# SpaceInvaders-v21-OtherMill-DoubleSided.net
KiCad netlist of a schematic drawn in EAGLE
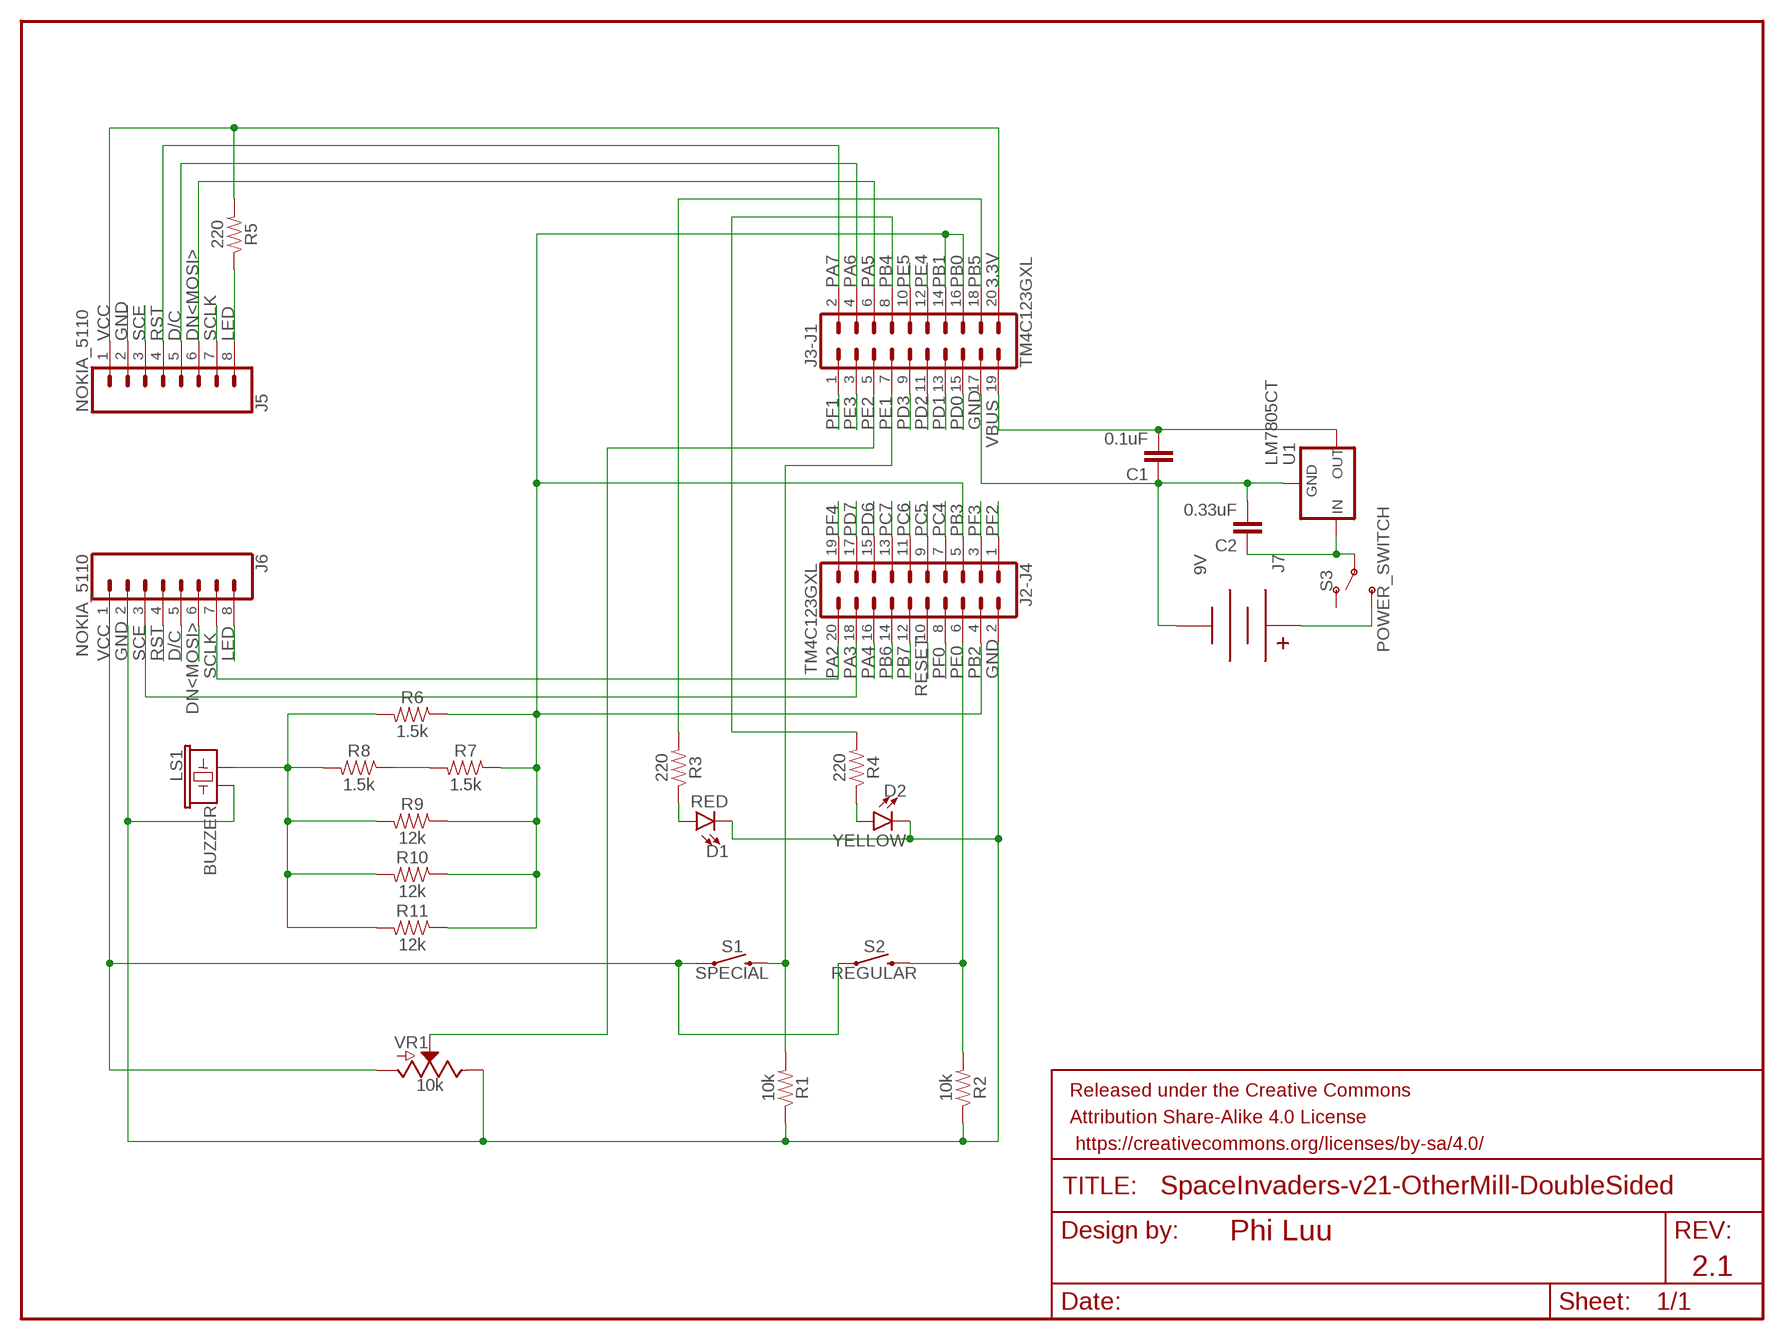
[diagram p0: schematic, sheet 1]

(export (version "E")
  (design (tool "Eeschema 10.0.6"))
  (components
    (comp (ref "C1")
      (value "0.1uF")
      (footprint "eagle-import:CAP-PTH-SMALL-KIT")
      (libsource (lib "eagle-import") (part "0.1UF-KIT-EZ-50V-20%"))
    )
    (comp (ref "C2")
      (value "0.33uF")
      (footprint "eagle-import:CAP-PTH-SMALL-KIT")
      (libsource (lib "eagle-import") (part "0.1UF-KIT-EZ-50V-20%"))
    )
    (comp (ref "D1")
      (value "RED")
      (footprint "eagle-import:LED_5MM")
      (libsource (lib "eagle-import") (part "LED5MM"))
    )
    (comp (ref "D2")
      (value "YELLOW")
      (footprint "eagle-import:LED_5MM")
      (libsource (lib "eagle-import") (part "LED5MM"))
    )
    (comp (ref "FRAME1")
      (value "FRAME-LETTER")
      (footprint "eagle-import:CREATIVE_COMMONS")
      (libsource (lib "eagle-import") (part "FRAME-LETTER"))
    )
    (comp (ref "J2-J4")
      (value "TM4C123GXL")
      (footprint "eagle-import:2X10")
      (libsource (lib "eagle-import") (part "CONN_10X2"))
    )
    (comp (ref "J3-J1")
      (value "TM4C123GXL")
      (footprint "eagle-import:2X10")
      (libsource (lib "eagle-import") (part "CONN_10X2"))
    )
    (comp (ref "J5")
      (value "NOKIA_5110")
      (footprint "eagle-import:1X08")
      (libsource (lib "eagle-import") (part "CONN_08{dblquote}"))
    )
    (comp (ref "J6")
      (value "NOKIA_5110")
      (footprint "eagle-import:1X08")
      (libsource (lib "eagle-import") (part "CONN_08{dblquote}"))
    )
    (comp (ref "J7")
      (value "9V")
      (footprint "eagle-import:BC9VPC")
      (libsource (lib "eagle-import") (part "BC9VPC"))
    )
    (comp (ref "LS1")
      (value "BUZZER")
      (footprint "eagle-import:BUZZER-12MM")
      (libsource (lib "eagle-import") (part "BUZZER-PTH"))
    )
    (comp (ref "R1")
      (value "10k")
      (footprint "eagle-import:AXIAL-0.3")
      (libsource (lib "eagle-import") (part "10KOHM-HORIZ-1/4W-5%"))
    )
    (comp (ref "R2")
      (value "10k")
      (footprint "eagle-import:AXIAL-0.3")
      (libsource (lib "eagle-import") (part "10KOHM-HORIZ-1/4W-5%"))
    )
    (comp (ref "R3")
      (value "220")
      (footprint "eagle-import:AXIAL-0.3")
      (libsource (lib "eagle-import") (part "1KOHM-HORIZ-1/4W-5%"))
    )
    (comp (ref "R4")
      (value "220")
      (footprint "eagle-import:AXIAL-0.3")
      (libsource (lib "eagle-import") (part "1KOHM-HORIZ-1/4W-5%"))
    )
    (comp (ref "R5")
      (value "220")
      (footprint "eagle-import:AXIAL-0.3")
      (libsource (lib "eagle-import") (part "1KOHM-HORIZ-1/4W-5%"))
    )
    (comp (ref "R6")
      (value "1.5k")
      (footprint "eagle-import:AXIAL-0.3")
      (libsource (lib "eagle-import") (part "1KOHM-HORIZ-1/4W-5%"))
    )
    (comp (ref "R7")
      (value "1.5k")
      (footprint "eagle-import:AXIAL-0.3")
      (libsource (lib "eagle-import") (part "1KOHM-HORIZ-1/4W-5%"))
    )
    (comp (ref "R8")
      (value "1.5k")
      (footprint "eagle-import:AXIAL-0.3")
      (libsource (lib "eagle-import") (part "1KOHM-HORIZ-1/4W-5%"))
    )
    (comp (ref "R9")
      (value "12k")
      (footprint "eagle-import:AXIAL-0.3")
      (libsource (lib "eagle-import") (part "1KOHM-HORIZ-1/4W-5%"))
    )
    (comp (ref "R10")
      (value "12k")
      (footprint "eagle-import:AXIAL-0.3")
      (libsource (lib "eagle-import") (part "1KOHM-HORIZ-1/4W-5%"))
    )
    (comp (ref "R11")
      (value "12k")
      (footprint "eagle-import:AXIAL-0.3")
      (libsource (lib "eagle-import") (part "1KOHM-HORIZ-1/4W-5%"))
    )
    (comp (ref "S1")
      (value "SPECIAL")
      (footprint "eagle-import:TACTILE_SWITCH_PTH_6.0MM")
      (libsource (lib "eagle-import") (part "MOMENTARY-SWITCH-SPST-PTH-6.0MM"))
    )
    (comp (ref "S2")
      (value "REGULAR")
      (footprint "eagle-import:TACTILE_SWITCH_PTH_6.0MM")
      (libsource (lib "eagle-import") (part "MOMENTARY-SWITCH-SPST-PTH-6.0MM"))
    )
    (comp (ref "S3")
      (value "POWER_SWITCH")
      (footprint "eagle-import:SWITCH_SPDT_PTH_11.6X4.0MM")
      (libsource (lib "eagle-import") (part "SWITCH-SPDT-PTH-11.6X4.0MM"))
    )
    (comp (ref "U1")
      (value "LM7805CT")
      (footprint "eagle-import:TO-220-ALT")
      (libsource (lib "eagle-import") (part "V_REG_78XX-TO-220"))
    )
    (comp (ref "VR1")
      (value "10k")
      (footprint "eagle-import:SLIDER-MEDIUM")
      (libsource (lib "eagle-import") (part "POTENTIOMETER_SLIDE-30MM-1/10W-20%"))
    )
  )
  (nets
    (net (code "1") (name "/3.3V") (class "Default")
      (node (ref "J3-J1") (pin "20") (pinfunction "20_20") (pintype "passive"))
      (node (ref "J5") (pin "1") (pinfunction "1_1") (pintype "passive"))
      (node (ref "J6") (pin "1") (pinfunction "1_1") (pintype "passive"))
      (node (ref "R5") (pin "P$2") (pinfunction "2_P$2") (pintype "passive"))
      (node (ref "S1") (pin "1") (pinfunction "1_1") (pintype "passive"))
      (node (ref "S2") (pin "1") (pinfunction "1_1") (pintype "passive"))
      (node (ref "VR1") (pin "BOTTOM") (pinfunction "A_BOTTOM") (pintype "passive"))
    )
    (net (code "2") (name "/GND") (class "Default")
      (node (ref "C1") (pin "1") (pinfunction "1_1") (pintype "passive"))
      (node (ref "C2") (pin "2") (pinfunction "2_2") (pintype "passive"))
      (node (ref "D1") (pin "K") (pinfunction "C_K") (pintype "passive"))
      (node (ref "D2") (pin "K") (pinfunction "C_K") (pintype "passive"))
      (node (ref "J2-J4") (pin "2") (pinfunction "2_2") (pintype "passive"))
      (node (ref "J3-J1") (pin "17") (pinfunction "17_17") (pintype "passive"))
      (node (ref "J5") (pin "2") (pinfunction "2_2") (pintype "passive"))
      (node (ref "J6") (pin "2") (pinfunction "2_2") (pintype "passive"))
      (node (ref "J7") (pin "V-") (pinfunction "V-_V-") (pintype "bidirectional"))
      (node (ref "LS1") (pin "-") (pinfunction "2_-") (pintype "passive"))
      (node (ref "R1") (pin "P$1") (pinfunction "1_P$1") (pintype "passive"))
      (node (ref "R2") (pin "P$1") (pinfunction "1_P$1") (pintype "passive"))
      (node (ref "U1") (pin "GND") (pinfunction "GND_GND") (pintype "input"))
      (node (ref "VR1") (pin "TOP") (pinfunction "E_TOP") (pintype "passive"))
    )
    (net (code "3") (name "/LED") (class "Default")
      (node (ref "J5") (pin "8") (pinfunction "8_8") (pintype "passive"))
      (node (ref "J6") (pin "8") (pinfunction "8_8") (pintype "passive"))
      (node (ref "R5") (pin "P$1") (pinfunction "1_P$1") (pintype "passive"))
    )
    (net (code "4") (name "/PA2") (class "Default")
      (node (ref "J2-J4") (pin "20") (pinfunction "20_20") (pintype "passive"))
      (node (ref "J5") (pin "7") (pinfunction "7_7") (pintype "passive"))
      (node (ref "J6") (pin "7") (pinfunction "7_7") (pintype "passive"))
    )
    (net (code "5") (name "/PA3") (class "Default")
      (node (ref "J2-J4") (pin "18") (pinfunction "18_18") (pintype "passive"))
      (node (ref "J5") (pin "3") (pinfunction "3_3") (pintype "passive"))
      (node (ref "J6") (pin "3") (pinfunction "3_3") (pintype "passive"))
    )
    (net (code "6") (name "/PA4") (class "Default")
      (node (ref "J2-J4") (pin "16") (pinfunction "16_16") (pintype "passive"))
    )
    (net (code "7") (name "/PA5") (class "Default")
      (node (ref "J3-J1") (pin "6") (pinfunction "6_6") (pintype "passive"))
      (node (ref "J5") (pin "6") (pinfunction "6_6") (pintype "passive"))
      (node (ref "J6") (pin "6") (pinfunction "6_6") (pintype "passive"))
    )
    (net (code "8") (name "/PA6") (class "Default")
      (node (ref "J3-J1") (pin "4") (pinfunction "4_4") (pintype "passive"))
      (node (ref "J5") (pin "5") (pinfunction "5_5") (pintype "passive"))
      (node (ref "J6") (pin "5") (pinfunction "5_5") (pintype "passive"))
    )
    (net (code "9") (name "/PA7") (class "Default")
      (node (ref "J3-J1") (pin "2") (pinfunction "2_2") (pintype "passive"))
      (node (ref "J5") (pin "4") (pinfunction "4_4") (pintype "passive"))
      (node (ref "J6") (pin "4") (pinfunction "4_4") (pintype "passive"))
    )
    (net (code "10") (name "/PB4") (class "Default")
      (node (ref "J3-J1") (pin "8") (pinfunction "8_8") (pintype "passive"))
      (node (ref "R4") (pin "P$2") (pinfunction "2_P$2") (pintype "passive"))
    )
    (net (code "11") (name "/PB5") (class "Default")
      (node (ref "J3-J1") (pin "18") (pinfunction "18_18") (pintype "passive"))
      (node (ref "R3") (pin "P$2") (pinfunction "2_P$2") (pintype "passive"))
    )
    (net (code "12") (name "/PB6") (class "Default")
      (node (ref "J2-J4") (pin "14") (pinfunction "14_14") (pintype "passive"))
    )
    (net (code "13") (name "/PB7") (class "Default")
      (node (ref "J2-J4") (pin "12") (pinfunction "12_12") (pintype "passive"))
    )
    (net (code "14") (name "/PC4") (class "Default")
      (node (ref "J2-J4") (pin "7") (pinfunction "7_7") (pintype "passive"))
    )
    (net (code "15") (name "/PC5") (class "Default")
      (node (ref "J2-J4") (pin "9") (pinfunction "9_9") (pintype "passive"))
    )
    (net (code "16") (name "/PC6") (class "Default")
      (node (ref "J2-J4") (pin "11") (pinfunction "11_11") (pintype "passive"))
    )
    (net (code "17") (name "/PC7") (class "Default")
      (node (ref "J2-J4") (pin "13") (pinfunction "13_13") (pintype "passive"))
    )
    (net (code "18") (name "/PD0") (class "Default")
      (node (ref "J3-J1") (pin "15") (pinfunction "15_15") (pintype "passive"))
    )
    (net (code "19") (name "/PD1") (class "Default")
      (node (ref "J3-J1") (pin "13") (pinfunction "13_13") (pintype "passive"))
    )
    (net (code "20") (name "/PD2") (class "Default")
      (node (ref "J3-J1") (pin "11") (pinfunction "11_11") (pintype "passive"))
    )
    (net (code "21") (name "/PD3") (class "Default")
      (node (ref "J3-J1") (pin "9") (pinfunction "9_9") (pintype "passive"))
    )
    (net (code "22") (name "/PD6") (class "Default")
      (node (ref "J2-J4") (pin "15") (pinfunction "15_15") (pintype "passive"))
    )
    (net (code "23") (name "/PD7") (class "Default")
      (node (ref "J2-J4") (pin "17") (pinfunction "17_17") (pintype "passive"))
    )
    (net (code "24") (name "/PE0") (class "Default")
      (node (ref "J2-J4") (pin "6") (pinfunction "6_6") (pintype "passive"))
      (node (ref "R2") (pin "P$2") (pinfunction "2_P$2") (pintype "passive"))
      (node (ref "S2") (pin "3") (pinfunction "2_3") (pintype "passive"))
    )
    (net (code "25") (name "/PE1") (class "Default")
      (node (ref "J3-J1") (pin "7") (pinfunction "7_7") (pintype "passive"))
      (node (ref "R1") (pin "P$2") (pinfunction "2_P$2") (pintype "passive"))
      (node (ref "S1") (pin "3") (pinfunction "2_3") (pintype "passive"))
    )
    (net (code "26") (name "/PE2") (class "Default")
      (node (ref "J3-J1") (pin "5") (pinfunction "5_5") (pintype "passive"))
      (node (ref "VR1") (pin "WIPER") (pinfunction "S_WIPER") (pintype "passive"))
    )
    (net (code "27") (name "/PE3") (class "Default")
      (node (ref "J3-J1") (pin "3") (pinfunction "3_3") (pintype "passive"))
    )
    (net (code "28") (name "/PE4") (class "Default")
      (node (ref "J3-J1") (pin "12") (pinfunction "12_12") (pintype "passive"))
    )
    (net (code "29") (name "/PE5") (class "Default")
      (node (ref "J3-J1") (pin "10") (pinfunction "10_10") (pintype "passive"))
    )
    (net (code "30") (name "/PF0") (class "Default")
      (node (ref "J2-J4") (pin "8") (pinfunction "8_8") (pintype "passive"))
    )
    (net (code "31") (name "/PF1") (class "Default")
      (node (ref "J3-J1") (pin "1") (pinfunction "1_1") (pintype "passive"))
    )
    (net (code "32") (name "/PF2") (class "Default")
      (node (ref "J2-J4") (pin "1") (pinfunction "1_1") (pintype "passive"))
    )
    (net (code "33") (name "/PF3") (class "Default")
      (node (ref "J2-J4") (pin "3") (pinfunction "3_3") (pintype "passive"))
    )
    (net (code "34") (name "/PF4") (class "Default")
      (node (ref "J2-J4") (pin "19") (pinfunction "19_19") (pintype "passive"))
    )
    (net (code "35") (name "/RESET") (class "Default")
      (node (ref "J2-J4") (pin "10") (pinfunction "10_10") (pintype "passive"))
    )
    (net (code "36") (name "/VBUS") (class "Default")
      (node (ref "C1") (pin "2") (pinfunction "2_2") (pintype "passive"))
      (node (ref "J3-J1") (pin "19") (pinfunction "19_19") (pintype "passive"))
      (node (ref "U1") (pin "OUT") (pinfunction "OUT_OUT") (pintype "passive"))
    )
    (net (code "37") (name "Net-(LS1-1)") (class "Default")
      (node (ref "LS1") (pin "+") (pinfunction "1_+") (pintype "passive"))
      (node (ref "R10") (pin "P$2") (pinfunction "2_P$2") (pintype "passive"))
      (node (ref "R11") (pin "P$2") (pinfunction "2_P$2") (pintype "passive"))
      (node (ref "R6") (pin "P$2") (pinfunction "2_P$2") (pintype "passive"))
      (node (ref "R8") (pin "P$2") (pinfunction "2_P$2") (pintype "passive"))
      (node (ref "R9") (pin "P$2") (pinfunction "2_P$2") (pintype "passive"))
    )
    (net (code "38") (name "Net-(R3-1)") (class "Default")
      (node (ref "D1") (pin "A") (pinfunction "A_A") (pintype "passive"))
      (node (ref "R3") (pin "P$1") (pinfunction "1_P$1") (pintype "passive"))
    )
    (net (code "39") (name "Net-(R4-1)") (class "Default")
      (node (ref "D2") (pin "A") (pinfunction "A_A") (pintype "passive"))
      (node (ref "R4") (pin "P$1") (pinfunction "1_P$1") (pintype "passive"))
    )
    (net (code "40") (name "Net-(R7-2)") (class "Default")
      (node (ref "R7") (pin "P$2") (pinfunction "2_P$2") (pintype "passive"))
      (node (ref "R8") (pin "P$1") (pinfunction "1_P$1") (pintype "passive"))
    )
    (net (code "41") (name "Net-(R10-1)") (class "Default")
      (node (ref "J2-J4") (pin "4") (pinfunction "4_4") (pintype "passive"))
      (node (ref "J2-J4") (pin "5") (pinfunction "5_5") (pintype "passive"))
      (node (ref "J3-J1") (pin "14") (pinfunction "14_14") (pintype "passive"))
      (node (ref "J3-J1") (pin "16") (pinfunction "16_16") (pintype "passive"))
      (node (ref "R10") (pin "P$1") (pinfunction "1_P$1") (pintype "passive"))
      (node (ref "R11") (pin "P$1") (pinfunction "1_P$1") (pintype "passive"))
      (node (ref "R6") (pin "P$1") (pinfunction "1_P$1") (pintype "passive"))
      (node (ref "R7") (pin "P$1") (pinfunction "1_P$1") (pintype "passive"))
      (node (ref "R9") (pin "P$1") (pinfunction "1_P$1") (pintype "passive"))
    )
    (net (code "42") (name "Net-(S3-P)") (class "Default")
      (node (ref "C2") (pin "1") (pinfunction "1_1") (pintype "passive"))
      (node (ref "S3") (pin "2") (pinfunction "P_2") (pintype "passive"))
      (node (ref "U1") (pin "IN") (pinfunction "IN_IN") (pintype "input"))
    )
    (net (code "43") (name "Net-(S3-S)") (class "Default")
      (node (ref "J7") (pin "V+") (pinfunction "V+_V+") (pintype "bidirectional"))
      (node (ref "S3") (pin "3") (pinfunction "S_3") (pintype "passive"))
    )
    (net (code "44") (name "unconnected-(S3-O-Pad1)") (class "Default")
      (node (ref "S3") (pin "1") (pinfunction "O_1") (pintype "passive"))
    )
  )
)
